# ESP8266_IOT_Board_v1_0.net
KiCad netlist of a schematic drawn in EAGLE
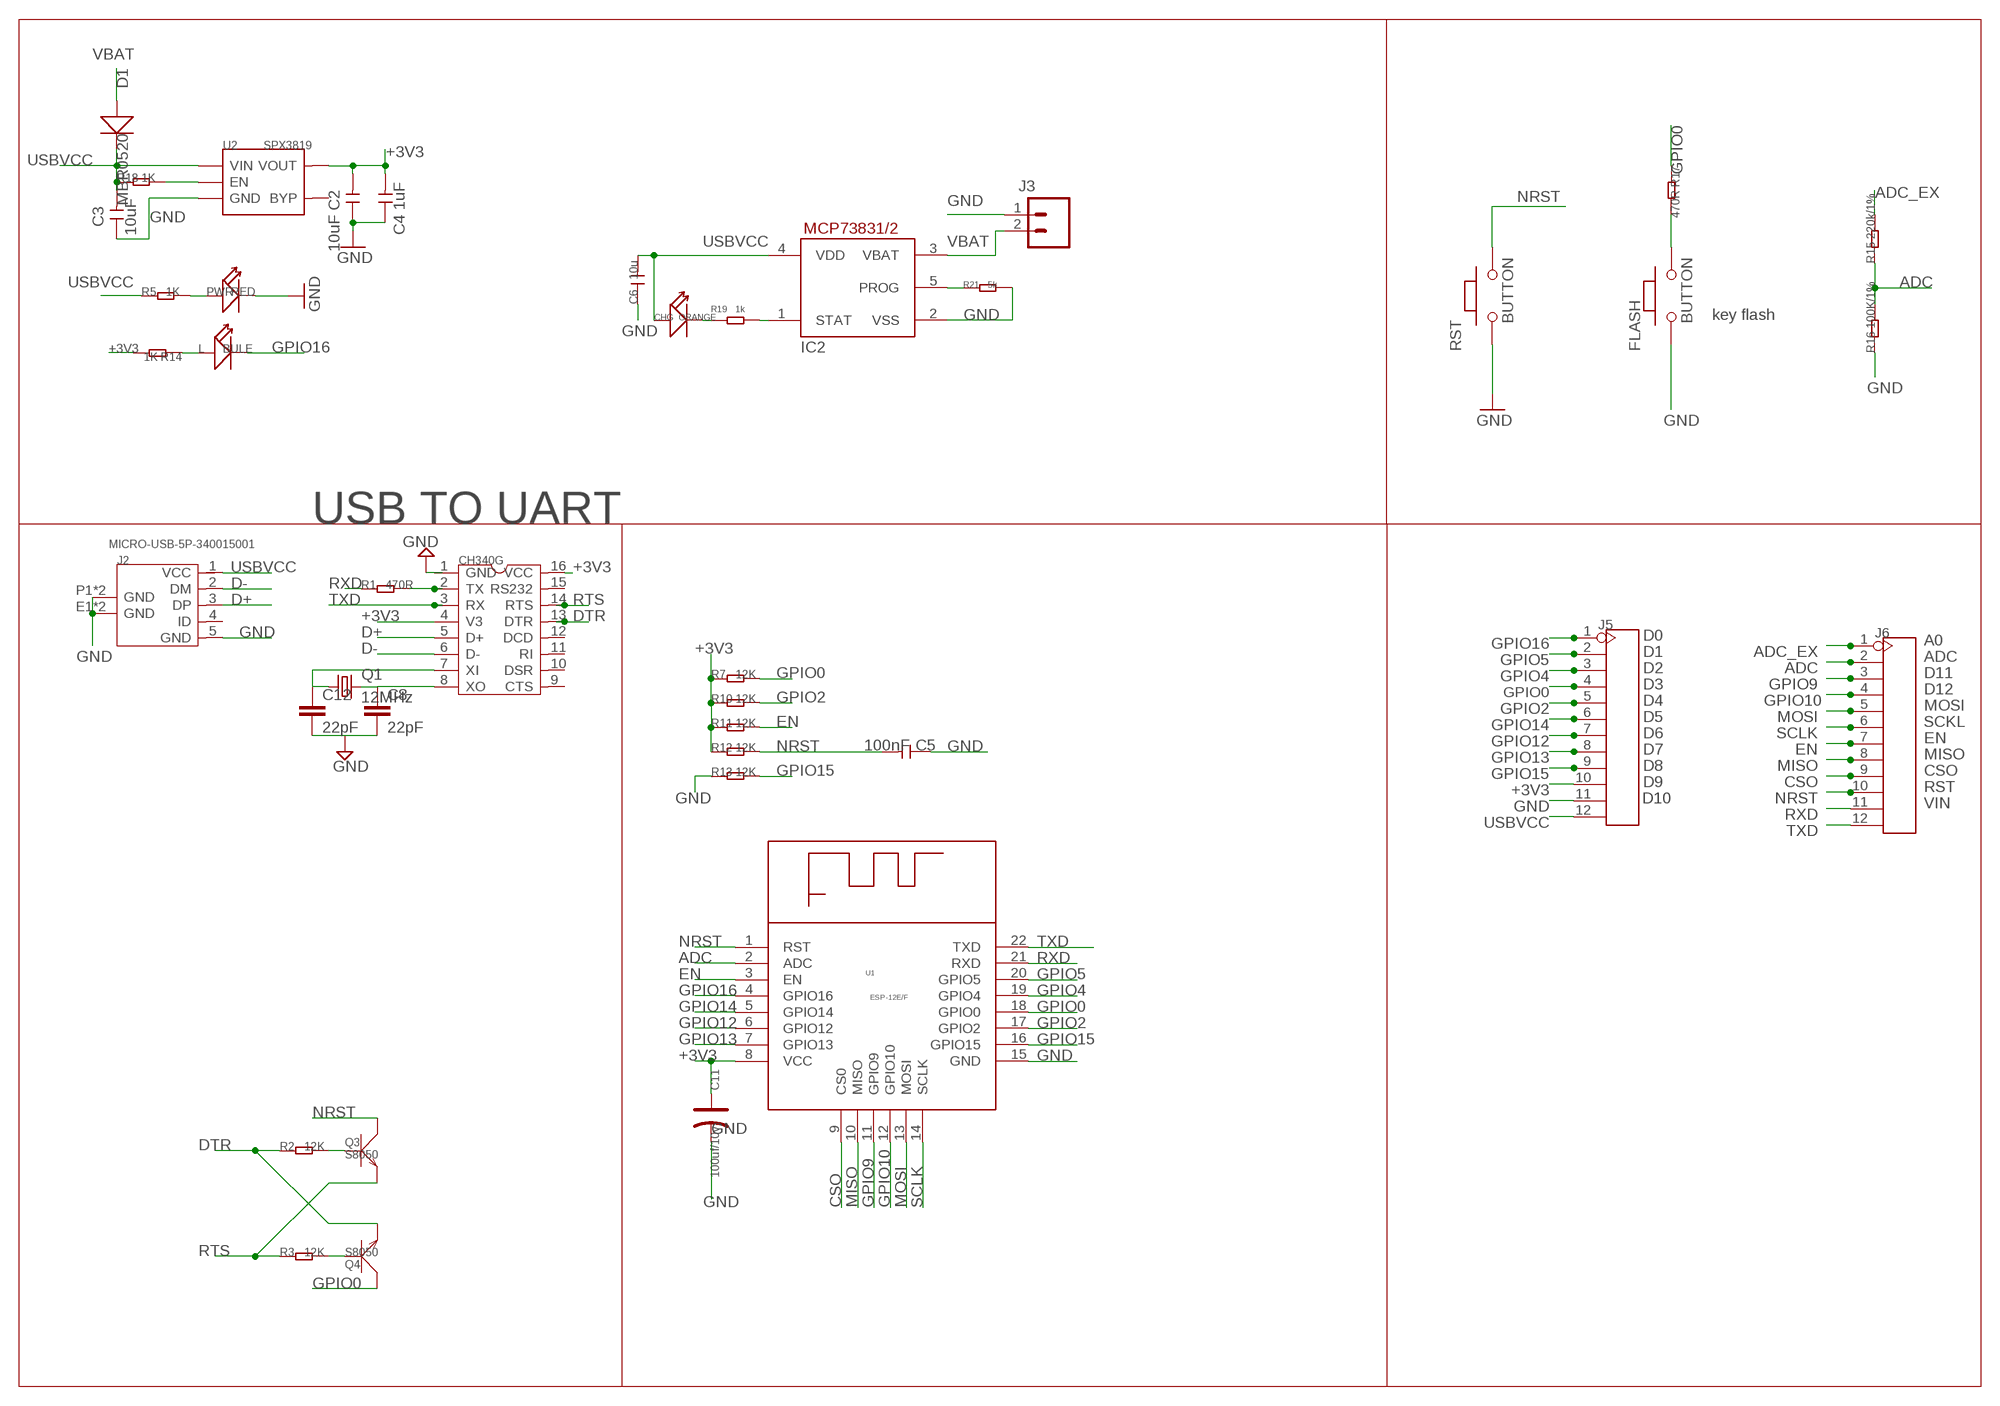
[diagram p0: schematic, sheet 1]

(export (version "E")
  (design (tool "Eeschema 10.0.6"))
  (components
    (comp (ref "C2")
      (value "10uF")
      (footprint "eagle-import:C0603")
      (libsource (lib "eagle-import") (part "C-0603"))
    )
    (comp (ref "C3")
      (value "10uF")
      (footprint "eagle-import:C0603")
      (libsource (lib "eagle-import") (part "C-0603"))
    )
    (comp (ref "C4")
      (value "1uF")
      (footprint "eagle-import:C0603")
      (libsource (lib "eagle-import") (part "C-0603"))
    )
    (comp (ref "C5")
      (value "100nF")
      (footprint "eagle-import:C0603")
      (libsource (lib "eagle-import") (part "C-0603"))
    )
    (comp (ref "C6")
      (value "10u")
      (footprint "eagle-import:C0603")
      (libsource (lib "eagle-import") (part "C-0603"))
    )
    (comp (ref "C8")
      (value "22pF")
      (footprint "eagle-import:0603-CAP")
      (libsource (lib "eagle-import") (part "CAP0603-CAP"))
    )
    (comp (ref "C11")
      (value "100uf/10v")
      (footprint "eagle-import:AVX-B")
      (libsource (lib "eagle-import") (part "CAP-AVX-B"))
    )
    (comp (ref "C12")
      (value "22pF")
      (footprint "eagle-import:0603-CAP")
      (libsource (lib "eagle-import") (part "CAP0603-CAP"))
    )
    (comp (ref "CH340G")
      (value "CH340GCH340G")
      (footprint "eagle-import:SOP-16")
      (libsource (lib "eagle-import") (part "CH340GCH340G"))
    )
    (comp (ref "CHG")
      (value "ORANGE")
      (footprint "eagle-import:D0603")
      (libsource (lib "eagle-import") (part "007-LED0603"))
    )
    (comp (ref "D1")
      (value "MBR0520")
      (footprint "eagle-import:SOD123")
      (libsource (lib "eagle-import") (part "D'1206'"))
    )
    (comp (ref "FLASH")
      (value "BUTTON")
      (footprint "eagle-import:157SW")
      (libsource (lib "eagle-import") (part "PB157"))
    )
    (comp (ref "IC2")
      (value "MCP73831/OT")
      (footprint "eagle-import:SOT23-5L")
      (libsource (lib "eagle-import") (part "MCP73831/OT"))
    )
    (comp (ref "J2")
      (value "MICRO-USB-5P-340015001")
      (footprint "eagle-import:B-SMD-5P")
      (libsource (lib "eagle-import") (part "MICRO-USB-5P-340015001"))
    )
    (comp (ref "J3")
      (value "M02-JST-2MM-SMT")
      (footprint "eagle-import:JST-2-SMD")
      (libsource (lib "eagle-import") (part "M02-JST-2MM-SMT"))
    )
    (comp (ref "J5")
      (value "HEADER-12P-2.54")
      (footprint "eagle-import:12P-2.54")
      (libsource (lib "eagle-import") (part "HEADER-12P-2.54"))
    )
    (comp (ref "J6")
      (value "HEADER-12P-2.54")
      (footprint "eagle-import:12P-2.54")
      (libsource (lib "eagle-import") (part "HEADER-12P-2.54"))
    )
    (comp (ref "L")
      (value "BULE")
      (footprint "eagle-import:LED-0603")
      (libsource (lib "eagle-import") (part "LED'0603'"))
    )
    (comp (ref "PWR")
      (value "RED")
      (footprint "eagle-import:LED-0603")
      (libsource (lib "eagle-import") (part "LED'0603'"))
    )
    (comp (ref "Q1")
      (value "12MHz")
      (footprint "eagle-import:HC49U70")
      (libsource (lib "eagle-import") (part "CRYSTALHC49U70"))
    )
    (comp (ref "Q3")
      (value "S8050")
      (footprint "eagle-import:SOT23")
      (libsource (lib "eagle-import") (part "TRANSISTOR-NPN-SOT23"))
    )
    (comp (ref "Q4")
      (value "S8050")
      (footprint "eagle-import:SOT23")
      (libsource (lib "eagle-import") (part "TRANSISTOR-NPN-SOT23"))
    )
    (comp (ref "R1")
      (value "470R")
      (footprint "eagle-import:R0603")
      (libsource (lib "eagle-import") (part "R-0603"))
    )
    (comp (ref "R2")
      (value "12K")
      (footprint "eagle-import:R0603")
      (libsource (lib "eagle-import") (part "R-0603"))
    )
    (comp (ref "R3")
      (value "12K")
      (footprint "eagle-import:R0603")
      (libsource (lib "eagle-import") (part "R-0603"))
    )
    (comp (ref "R5")
      (value "1K")
      (footprint "eagle-import:R0603")
      (libsource (lib "eagle-import") (part "R-0603"))
    )
    (comp (ref "R7")
      (value "12K")
      (footprint "eagle-import:R0603")
      (libsource (lib "eagle-import") (part "R-0603"))
    )
    (comp (ref "R10")
      (value "12K")
      (footprint "eagle-import:R0603")
      (libsource (lib "eagle-import") (part "R-0603"))
    )
    (comp (ref "R11")
      (value "12K")
      (footprint "eagle-import:R0603")
      (libsource (lib "eagle-import") (part "R-0603"))
    )
    (comp (ref "R12")
      (value "12K")
      (footprint "eagle-import:R0603")
      (libsource (lib "eagle-import") (part "R-0603"))
    )
    (comp (ref "R13")
      (value "12K")
      (footprint "eagle-import:R0603")
      (libsource (lib "eagle-import") (part "R-0603"))
    )
    (comp (ref "R14")
      (value "1K")
      (footprint "eagle-import:R0603")
      (libsource (lib "eagle-import") (part "R-0603"))
    )
    (comp (ref "R15")
      (value "220k/1%")
      (footprint "eagle-import:R0603")
      (libsource (lib "eagle-import") (part "R-0603"))
    )
    (comp (ref "R16")
      (value "100K/1%")
      (footprint "eagle-import:R0603")
      (libsource (lib "eagle-import") (part "R-0603"))
    )
    (comp (ref "R17")
      (value "470R")
      (footprint "eagle-import:R0603")
      (libsource (lib "eagle-import") (part "R-0603"))
    )
    (comp (ref "R18")
      (value "1K")
      (footprint "eagle-import:R0603")
      (libsource (lib "eagle-import") (part "R-0603"))
    )
    (comp (ref "R19")
      (value "1k")
      (footprint "eagle-import:R0603")
      (libsource (lib "eagle-import") (part "R-0603"))
    )
    (comp (ref "R21")
      (value "5k")
      (footprint "eagle-import:R0603")
      (libsource (lib "eagle-import") (part "R-0603"))
    )
    (comp (ref "RST")
      (value "BUTTON")
      (footprint "eagle-import:157SW")
      (libsource (lib "eagle-import") (part "PB157"))
    )
    (comp (ref "U1")
      (value "ESP-12E/F")
      (footprint "eagle-import:ESP-12E_F")
      (libsource (lib "eagle-import") (part "ESP-12E/F"))
    )
    (comp (ref "U2")
      (value "SPX3819")
      (footprint "eagle-import:SOT23-5")
      (libsource (lib "eagle-import") (part "SPX3819"))
    )
  )
  (nets
    (net (code "1") (name "/+3V3") (class "Default")
      (node (ref "C11") (pin "+") (pinfunction "+_+") (pintype "passive"))
      (node (ref "C2") (pin "2") (pinfunction "2_2") (pintype "passive"))
      (node (ref "C4") (pin "2") (pinfunction "2_2") (pintype "passive"))
      (node (ref "CH340G") (pin "16") (pinfunction "VCC_16") (pintype "output"))
      (node (ref "CH340G") (pin "4") (pinfunction "V3_4") (pintype "bidirectional"))
      (node (ref "J5") (pin "10") (pinfunction "10_10") (pintype "bidirectional"))
      (node (ref "R10") (pin "1") (pinfunction "1_1") (pintype "passive"))
      (node (ref "R11") (pin "1") (pinfunction "1_1") (pintype "passive"))
      (node (ref "R12") (pin "1") (pinfunction "1_1") (pintype "passive"))
      (node (ref "R14") (pin "2") (pinfunction "2_2") (pintype "passive"))
      (node (ref "R7") (pin "1") (pinfunction "1_1") (pintype "passive"))
      (node (ref "U1") (pin "8") (pinfunction "VCC_8") (pintype "bidirectional"))
      (node (ref "U2") (pin "5") (pinfunction "VOUT_5") (pintype "bidirectional"))
    )
    (net (code "2") (name "/ADC") (class "Default")
      (node (ref "J6") (pin "2") (pinfunction "2_2") (pintype "bidirectional"))
      (node (ref "R15") (pin "1") (pinfunction "1_1") (pintype "passive"))
      (node (ref "R16") (pin "2") (pinfunction "2_2") (pintype "passive"))
      (node (ref "U1") (pin "2") (pinfunction "ADC_2") (pintype "bidirectional"))
    )
    (net (code "3") (name "/ADC_EX") (class "Default")
      (node (ref "J6") (pin "1") (pinfunction "1_1") (pintype "bidirectional"))
      (node (ref "R15") (pin "2") (pinfunction "2_2") (pintype "passive"))
    )
    (net (code "4") (name "/CSO") (class "Default")
      (node (ref "J6") (pin "9") (pinfunction "9_9") (pintype "bidirectional"))
      (node (ref "U1") (pin "9") (pinfunction "CS0_9") (pintype "bidirectional"))
    )
    (net (code "5") (name "/D+") (class "Default")
      (node (ref "CH340G") (pin "5") (pinfunction "D+_5") (pintype "bidirectional"))
      (node (ref "J2") (pin "3") (pinfunction "DP_3") (pintype "bidirectional"))
    )
    (net (code "6") (name "/D-") (class "Default")
      (node (ref "CH340G") (pin "6") (pinfunction "D-_6") (pintype "bidirectional"))
      (node (ref "J2") (pin "2") (pinfunction "DM_2") (pintype "bidirectional"))
    )
    (net (code "7") (name "/DTR") (class "Default")
      (node (ref "CH340G") (pin "13") (pinfunction "DTR_13") (pintype "input"))
      (node (ref "Q4") (pin "2") (pinfunction "E_2") (pintype "passive"))
      (node (ref "R2") (pin "1") (pinfunction "1_1") (pintype "passive"))
    )
    (net (code "8") (name "/EN") (class "Default")
      (node (ref "J6") (pin "7") (pinfunction "7_7") (pintype "bidirectional"))
      (node (ref "R11") (pin "2") (pinfunction "2_2") (pintype "passive"))
      (node (ref "U1") (pin "3") (pinfunction "EN_3") (pintype "bidirectional"))
    )
    (net (code "9") (name "/GPIO0") (class "Default")
      (node (ref "J5") (pin "4") (pinfunction "4_4") (pintype "bidirectional"))
      (node (ref "Q4") (pin "3") (pinfunction "C_3") (pintype "passive"))
      (node (ref "R17") (pin "1") (pinfunction "1_1") (pintype "passive"))
      (node (ref "R7") (pin "2") (pinfunction "2_2") (pintype "passive"))
      (node (ref "U1") (pin "18") (pinfunction "GPIO0_18") (pintype "bidirectional"))
    )
    (net (code "10") (name "/GPIO2") (class "Default")
      (node (ref "J5") (pin "5") (pinfunction "5_5") (pintype "bidirectional"))
      (node (ref "R10") (pin "2") (pinfunction "2_2") (pintype "passive"))
      (node (ref "U1") (pin "17") (pinfunction "GPIO2_17") (pintype "bidirectional"))
    )
    (net (code "11") (name "/GPIO4") (class "Default")
      (node (ref "J5") (pin "3") (pinfunction "3_3") (pintype "bidirectional"))
      (node (ref "U1") (pin "19") (pinfunction "GPIO4_19") (pintype "bidirectional"))
    )
    (net (code "12") (name "/GPIO5") (class "Default")
      (node (ref "J5") (pin "2") (pinfunction "2_2") (pintype "bidirectional"))
      (node (ref "U1") (pin "20") (pinfunction "GPIO5_20") (pintype "bidirectional"))
    )
    (net (code "13") (name "/GPIO9") (class "Default")
      (node (ref "J6") (pin "3") (pinfunction "3_3") (pintype "bidirectional"))
      (node (ref "U1") (pin "11") (pinfunction "GPIO9_11") (pintype "bidirectional"))
    )
    (net (code "14") (name "/GPIO10") (class "Default")
      (node (ref "J6") (pin "4") (pinfunction "4_4") (pintype "bidirectional"))
      (node (ref "U1") (pin "12") (pinfunction "GPIO10_12") (pintype "bidirectional"))
    )
    (net (code "15") (name "/GPIO12") (class "Default")
      (node (ref "J5") (pin "7") (pinfunction "7_7") (pintype "bidirectional"))
      (node (ref "U1") (pin "6") (pinfunction "GPIO12_6") (pintype "bidirectional"))
    )
    (net (code "16") (name "/GPIO13") (class "Default")
      (node (ref "J5") (pin "8") (pinfunction "8_8") (pintype "bidirectional"))
      (node (ref "U1") (pin "7") (pinfunction "GPIO13_7") (pintype "bidirectional"))
    )
    (net (code "17") (name "/GPIO14") (class "Default")
      (node (ref "J5") (pin "6") (pinfunction "6_6") (pintype "bidirectional"))
      (node (ref "U1") (pin "5") (pinfunction "GPIO14_5") (pintype "bidirectional"))
    )
    (net (code "18") (name "/GPIO15") (class "Default")
      (node (ref "J5") (pin "9") (pinfunction "9_9") (pintype "bidirectional"))
      (node (ref "R13") (pin "2") (pinfunction "2_2") (pintype "passive"))
      (node (ref "U1") (pin "16") (pinfunction "GPIO15_16") (pintype "bidirectional"))
    )
    (net (code "19") (name "/GPIO16") (class "Default")
      (node (ref "J5") (pin "1") (pinfunction "1_1") (pintype "bidirectional"))
      (node (ref "L") (pin "-") (pinfunction "-_-") (pintype "passive"))
      (node (ref "U1") (pin "4") (pinfunction "GPIO16_4") (pintype "bidirectional"))
    )
    (net (code "20") (name "/MISO") (class "Default")
      (node (ref "J6") (pin "8") (pinfunction "8_8") (pintype "bidirectional"))
      (node (ref "U1") (pin "10") (pinfunction "MISO_10") (pintype "bidirectional"))
    )
    (net (code "21") (name "/MOSI") (class "Default")
      (node (ref "J6") (pin "5") (pinfunction "5_5") (pintype "bidirectional"))
      (node (ref "U1") (pin "13") (pinfunction "MOSI_13") (pintype "bidirectional"))
    )
    (net (code "22") (name "/NRST") (class "Default")
      (node (ref "C5") (pin "2") (pinfunction "2_2") (pintype "passive"))
      (node (ref "J6") (pin "10") (pinfunction "10_10") (pintype "bidirectional"))
      (node (ref "Q3") (pin "3") (pinfunction "C_3") (pintype "passive"))
      (node (ref "R12") (pin "2") (pinfunction "2_2") (pintype "passive"))
      (node (ref "RST") (pin "2") (pinfunction "2_2") (pintype "passive"))
      (node (ref "U1") (pin "1") (pinfunction "RST_1") (pintype "bidirectional"))
    )
    (net (code "23") (name "/RI") (class "Default")
      (node (ref "CH340G") (pin "11") (pinfunction "RI_11") (pintype "power_in"))
    )
    (net (code "24") (name "/RTS") (class "Default")
      (node (ref "CH340G") (pin "14") (pinfunction "RTS_14") (pintype "input"))
      (node (ref "Q3") (pin "2") (pinfunction "E_2") (pintype "passive"))
      (node (ref "R3") (pin "1") (pinfunction "1_1") (pintype "passive"))
    )
    (net (code "25") (name "/RXD") (class "Default")
      (node (ref "J6") (pin "11") (pinfunction "11_11") (pintype "bidirectional"))
      (node (ref "R1") (pin "1") (pinfunction "1_1") (pintype "passive"))
      (node (ref "U1") (pin "21") (pinfunction "RXD_21") (pintype "bidirectional"))
    )
    (net (code "26") (name "/SCLK") (class "Default")
      (node (ref "J6") (pin "6") (pinfunction "6_6") (pintype "bidirectional"))
      (node (ref "U1") (pin "14") (pinfunction "SCLK_14") (pintype "bidirectional"))
    )
    (net (code "27") (name "/TXD") (class "Default")
      (node (ref "CH340G") (pin "3") (pinfunction "RX_3") (pintype "bidirectional"))
      (node (ref "J6") (pin "12") (pinfunction "12_12") (pintype "bidirectional"))
      (node (ref "U1") (pin "22") (pinfunction "TXD_22") (pintype "bidirectional"))
    )
    (net (code "28") (name "/USBVCC") (class "Default")
      (node (ref "C3") (pin "2") (pinfunction "2_2") (pintype "passive"))
      (node (ref "C6") (pin "2") (pinfunction "2_2") (pintype "passive"))
      (node (ref "CHG") (pin "+") (pinfunction "+_+") (pintype "passive"))
      (node (ref "D1") (pin "-") (pinfunction "-_-") (pintype "passive"))
      (node (ref "IC2") (pin "4") (pinfunction "VDD_4") (pintype "power_in"))
      (node (ref "J2") (pin "1") (pinfunction "VCC_1") (pintype "bidirectional"))
      (node (ref "J5") (pin "12") (pinfunction "12_12") (pintype "bidirectional"))
      (node (ref "R18") (pin "1") (pinfunction "1_1") (pintype "passive"))
      (node (ref "R5") (pin "1") (pinfunction "1_1") (pintype "passive"))
      (node (ref "U2") (pin "1") (pinfunction "VIN_1") (pintype "bidirectional"))
    )
    (net (code "29") (name "/VBAT") (class "Default")
      (node (ref "D1") (pin "+") (pinfunction "+_+") (pintype "passive"))
      (node (ref "IC2") (pin "3") (pinfunction "VBAT_3") (pintype "bidirectional"))
      (node (ref "J3") (pin "2") (pinfunction "2_2") (pintype "passive"))
    )
    (net (code "30") (name "GND") (class "Default")
      (node (ref "C11") (pin "-") (pinfunction "-_-") (pintype "passive"))
      (node (ref "C12") (pin "2") (pinfunction "2_2") (pintype "passive"))
      (node (ref "C2") (pin "1") (pinfunction "1_1") (pintype "passive"))
      (node (ref "C3") (pin "1") (pinfunction "1_1") (pintype "passive"))
      (node (ref "C4") (pin "1") (pinfunction "1_1") (pintype "passive"))
      (node (ref "C5") (pin "1") (pinfunction "1_1") (pintype "passive"))
      (node (ref "C6") (pin "1") (pinfunction "1_1") (pintype "passive"))
      (node (ref "C8") (pin "2") (pinfunction "2_2") (pintype "passive"))
      (node (ref "CH340G") (pin "1") (pinfunction "GND_1") (pintype "bidirectional"))
      (node (ref "FLASH") (pin "1") (pinfunction "1_1") (pintype "passive"))
      (node (ref "IC2") (pin "2") (pinfunction "VSS_2") (pintype "power_in"))
      (node (ref "J2") (pin "5") (pinfunction "GND_5") (pintype "bidirectional"))
      (node (ref "J2") (pin "E1") (pinfunction "GND_E1") (pintype "bidirectional"))
      (node (ref "J2") (pin "E2") (pinfunction "GND_E2") (pintype "bidirectional"))
      (node (ref "J2") (pin "P1") (pinfunction "GND_P1") (pintype "bidirectional"))
      (node (ref "J2") (pin "P2") (pinfunction "GND_P2") (pintype "bidirectional"))
      (node (ref "J3") (pin "1") (pinfunction "1_1") (pintype "passive"))
      (node (ref "J5") (pin "11") (pinfunction "11_11") (pintype "bidirectional"))
      (node (ref "PWR") (pin "-") (pinfunction "-_-") (pintype "passive"))
      (node (ref "R13") (pin "1") (pinfunction "1_1") (pintype "passive"))
      (node (ref "R16") (pin "1") (pinfunction "1_1") (pintype "passive"))
      (node (ref "R21") (pin "2") (pinfunction "2_2") (pintype "passive"))
      (node (ref "RST") (pin "1") (pinfunction "1_1") (pintype "passive"))
      (node (ref "U1") (pin "15") (pinfunction "GND_15") (pintype "bidirectional"))
      (node (ref "U2") (pin "2") (pinfunction "GND_2") (pintype "bidirectional"))
    )
    (net (code "31") (name "Net-(CH340G-TX)") (class "Default")
      (node (ref "CH340G") (pin "2") (pinfunction "TX_2") (pintype "bidirectional"))
      (node (ref "R1") (pin "2") (pinfunction "2_2") (pintype "passive"))
    )
    (net (code "32") (name "Net-(CH340G-XI)") (class "Default")
      (node (ref "C12") (pin "1") (pinfunction "1_1") (pintype "passive"))
      (node (ref "CH340G") (pin "7") (pinfunction "XI_7") (pintype "power_in"))
      (node (ref "Q1") (pin "1") (pinfunction "1_1") (pintype "passive"))
    )
    (net (code "33") (name "Net-(CH340G-XO)") (class "Default")
      (node (ref "C8") (pin "1") (pinfunction "1_1") (pintype "passive"))
      (node (ref "CH340G") (pin "8") (pinfunction "XO_8") (pintype "input"))
      (node (ref "Q1") (pin "2") (pinfunction "2_2") (pintype "passive"))
    )
    (net (code "34") (name "Net-(CHG-Pad-)") (class "Default")
      (node (ref "CHG") (pin "-") (pinfunction "-_-") (pintype "passive"))
      (node (ref "R19") (pin "1") (pinfunction "1_1") (pintype "passive"))
    )
    (net (code "35") (name "Net-(FLASH-Pad2)") (class "Default")
      (node (ref "FLASH") (pin "2") (pinfunction "2_2") (pintype "passive"))
      (node (ref "R17") (pin "2") (pinfunction "2_2") (pintype "passive"))
    )
    (net (code "36") (name "Net-(IC2-PROG)") (class "Default")
      (node (ref "IC2") (pin "5") (pinfunction "PROG_5") (pintype "input"))
      (node (ref "R21") (pin "1") (pinfunction "1_1") (pintype "passive"))
    )
    (net (code "37") (name "Net-(IC2-STAT)") (class "Default")
      (node (ref "IC2") (pin "1") (pinfunction "STAT_1") (pintype "output"))
      (node (ref "R19") (pin "2") (pinfunction "2_2") (pintype "passive"))
    )
    (net (code "38") (name "Net-(L-Pad+)") (class "Default")
      (node (ref "L") (pin "+") (pinfunction "+_+") (pintype "passive"))
      (node (ref "R14") (pin "1") (pinfunction "1_1") (pintype "passive"))
    )
    (net (code "39") (name "Net-(PWR-Pad+)") (class "Default")
      (node (ref "PWR") (pin "+") (pinfunction "+_+") (pintype "passive"))
      (node (ref "R5") (pin "2") (pinfunction "2_2") (pintype "passive"))
    )
    (net (code "40") (name "Net-(Q3-B)") (class "Default")
      (node (ref "Q3") (pin "1") (pinfunction "B_1") (pintype "passive"))
      (node (ref "R2") (pin "2") (pinfunction "2_2") (pintype "passive"))
    )
    (net (code "41") (name "Net-(Q4-B)") (class "Default")
      (node (ref "Q4") (pin "1") (pinfunction "B_1") (pintype "passive"))
      (node (ref "R3") (pin "2") (pinfunction "2_2") (pintype "passive"))
    )
    (net (code "42") (name "Net-(U2-EN)") (class "Default")
      (node (ref "R18") (pin "2") (pinfunction "2_2") (pintype "passive"))
      (node (ref "U2") (pin "3") (pinfunction "EN_3") (pintype "bidirectional"))
    )
    (net (code "43") (name "unconnected-(CH340G-CTS-Pad9)") (class "Default")
      (node (ref "CH340G") (pin "9") (pinfunction "CTS_9") (pintype "bidirectional"))
    )
    (net (code "44") (name "unconnected-(CH340G-DCD-Pad12)") (class "Default")
      (node (ref "CH340G") (pin "12") (pinfunction "DCD_12") (pintype "output"))
    )
    (net (code "45") (name "unconnected-(CH340G-DSR-Pad10)") (class "Default")
      (node (ref "CH340G") (pin "10") (pinfunction "DSR_10") (pintype "bidirectional"))
    )
    (net (code "46") (name "unconnected-(CH340G-RS232-Pad15)") (class "Default")
      (node (ref "CH340G") (pin "15") (pinfunction "RS232_15") (pintype "input"))
    )
    (net (code "47") (name "unconnected-(J2-ID-Pad4)") (class "Default")
      (node (ref "J2") (pin "4") (pinfunction "ID_4") (pintype "bidirectional"))
    )
    (net (code "48") (name "unconnected-(U2-BYP-Pad4)") (class "Default")
      (node (ref "U2") (pin "4") (pinfunction "BYP_4") (pintype "bidirectional"))
    )
  )
)
